# Out3.net
KiCad netlist of a schematic drawn in Altium Designer
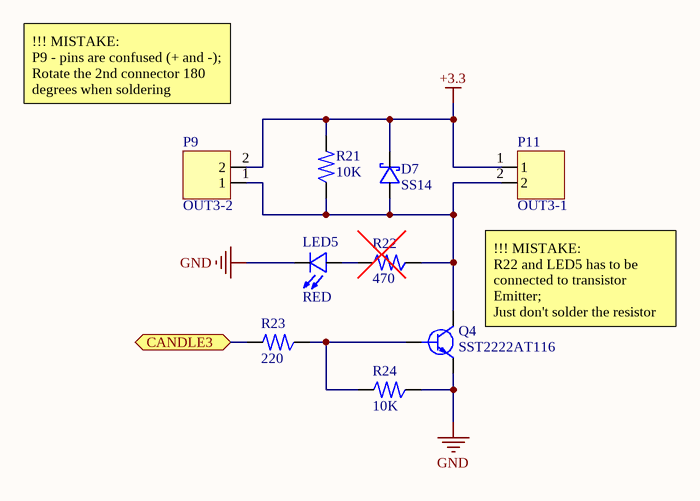
[diagram p0: Out3.SchDoc]

(export (version "E")
  (design (tool "Eeschema 10.0.6"))
  (components
    (comp (ref "D7")
      (value "SS14")
      (footprint "SMT_DIODE_SCHTKY_VISHAI")
      (description "SMT Diode Schottky Vishay DO-214AC SS14-M3/5AT IF=1A VR=40 V FV=0.5VG")
      (libsource (lib "SMT_DIODE_SCHTKY_VISHAI") (part "SMT_DIODE_SCHTKY_VISHAI"))
    )
    (comp (ref "LED5")
      (value "RED")
      (footprint "SMT_LED_0805(2012)_WURTH")
      (description "LED 0805(2012) 20mA 2V 150080YS75000 by Wurth Elektronik")
      (libsource (lib "SMT_LED_0805(2012)_WURTH") (part "SMT_LED_0805(2012)_WURTH"))
    )
    (comp (ref "P9")
      (value "OUT3-2")
      (footprint "THT_CON_WAFER_2P_NEL_2217S-02-WH2")
      (description "Connector Wafer NELTRON 2-Pins Pitch-2.54mm 250V/3A 2217S-02-WH2")
      (libsource (lib "") (part "THT_CON_WAFER_2P_NEL_2217S-02-WH2_1"))
    )
    (comp (ref "P11")
      (value "OUT3-1")
      (footprint "THT_CON_WAFER_2P_NEL_2217S-02-WH2")
      (description "Connector Wafer NELTRON 2-Pins Pitch-2.54mm 250V/3A 2217S-02-WH2")
      (libsource (lib "THT_CON_WAFER_2P_NEL_2217S-02-WH2") (part "THT_CON_WAFER_2P_NEL_2217S-02-WH2"))
    )
    (comp (ref "Q4")
      (value "SST2222AT116")
      (footprint "SMT_TRANS_SST2222AT116_SOT23")
      (description "Transistor NPN SST2222AT116 SOT23 700mA 40V")
      (libsource (lib "SMT_TRANS_SST2222AT116_SOT23") (part "SMT_TRANS_SST2222AT116_SOT23"))
    )
    (comp (ref "R21")
      (value "10K")
      (footprint "SMT_RES_0805(2012)")
      (description "0805(2012) Resistor 1/4-1/8W 150V 2A")
      (libsource (lib "SMT_RES_0805(2012)") (part "SMT_RES_0805(2012)"))
    )
    (comp (ref "R22")
      (value "470")
      (footprint "SMT_RES_0805(2012)")
      (description "0805(2012) Resistor 1/4-1/8W 150V 2A")
      (libsource (lib "SMT_RES_0805(2012)") (part "SMT_RES_0805(2012)"))
    )
    (comp (ref "R23")
      (value "220")
      (footprint "SMT_RES_0805(2012)")
      (description "0805(2012) Resistor 1/4-1/8W 150V 2A")
      (libsource (lib "SMT_RES_0805(2012)") (part "SMT_RES_0805(2012)"))
    )
    (comp (ref "R24")
      (value "10K")
      (footprint "SMT_RES_0805(2012)")
      (description "0805(2012) Resistor 1/4-1/8W 150V 2A")
      (libsource (lib "SMT_RES_0805(2012)") (part "SMT_RES_0805(2012)"))
    )
  )
  (nets
    (net (code "1") (name "+3.3") (class "Default")
      (node (ref "D7") (pin "2") (pinfunction "2_2") (pintype "passive"))
      (node (ref "P11") (pin "1") (pinfunction "1_1") (pintype "passive"))
      (node (ref "P9") (pin "2") (pinfunction "2_2") (pintype "passive"))
      (node (ref "R21") (pin "1") (pinfunction "1_1") (pintype "passive"))
    )
    (net (code "2") (name "/CANDLE3") (class "Default")
      (node (ref "R23") (pin "1") (pinfunction "1_1") (pintype "passive"))
    )
    (net (code "3") (name "GND") (class "Default")
      (node (ref "LED5") (pin "1") (pinfunction "1_1") (pintype "passive"))
      (node (ref "Q4") (pin "1") (pinfunction "E_1") (pintype "passive"))
      (node (ref "R24") (pin "2") (pinfunction "2_2") (pintype "passive"))
    )
    (net (code "4") (name "Net-(LED5-Pad2)") (class "Default")
      (node (ref "LED5") (pin "2") (pinfunction "2_2") (pintype "passive"))
      (node (ref "R22") (pin "1") (pinfunction "1_1") (pintype "passive"))
    )
    (net (code "5") (name "Net-(Q4-B)") (class "Default")
      (node (ref "Q4") (pin "2") (pinfunction "B_2") (pintype "passive"))
      (node (ref "R23") (pin "2") (pinfunction "2_2") (pintype "passive"))
      (node (ref "R24") (pin "1") (pinfunction "1_1") (pintype "passive"))
    )
    (net (code "6") (name "Net-(Q4-C)") (class "Default")
      (node (ref "D7") (pin "1") (pinfunction "1_1") (pintype "passive"))
      (node (ref "P11") (pin "2") (pinfunction "2_2") (pintype "passive"))
      (node (ref "P9") (pin "1") (pinfunction "1_1") (pintype "passive"))
      (node (ref "Q4") (pin "3") (pinfunction "C_3") (pintype "passive"))
      (node (ref "R21") (pin "2") (pinfunction "2_2") (pintype "passive"))
      (node (ref "R22") (pin "2") (pinfunction "2_2") (pintype "passive"))
    )
  )
)
